# PERIPHERAL.net
KiCad netlist of a schematic drawn in Altium Designer
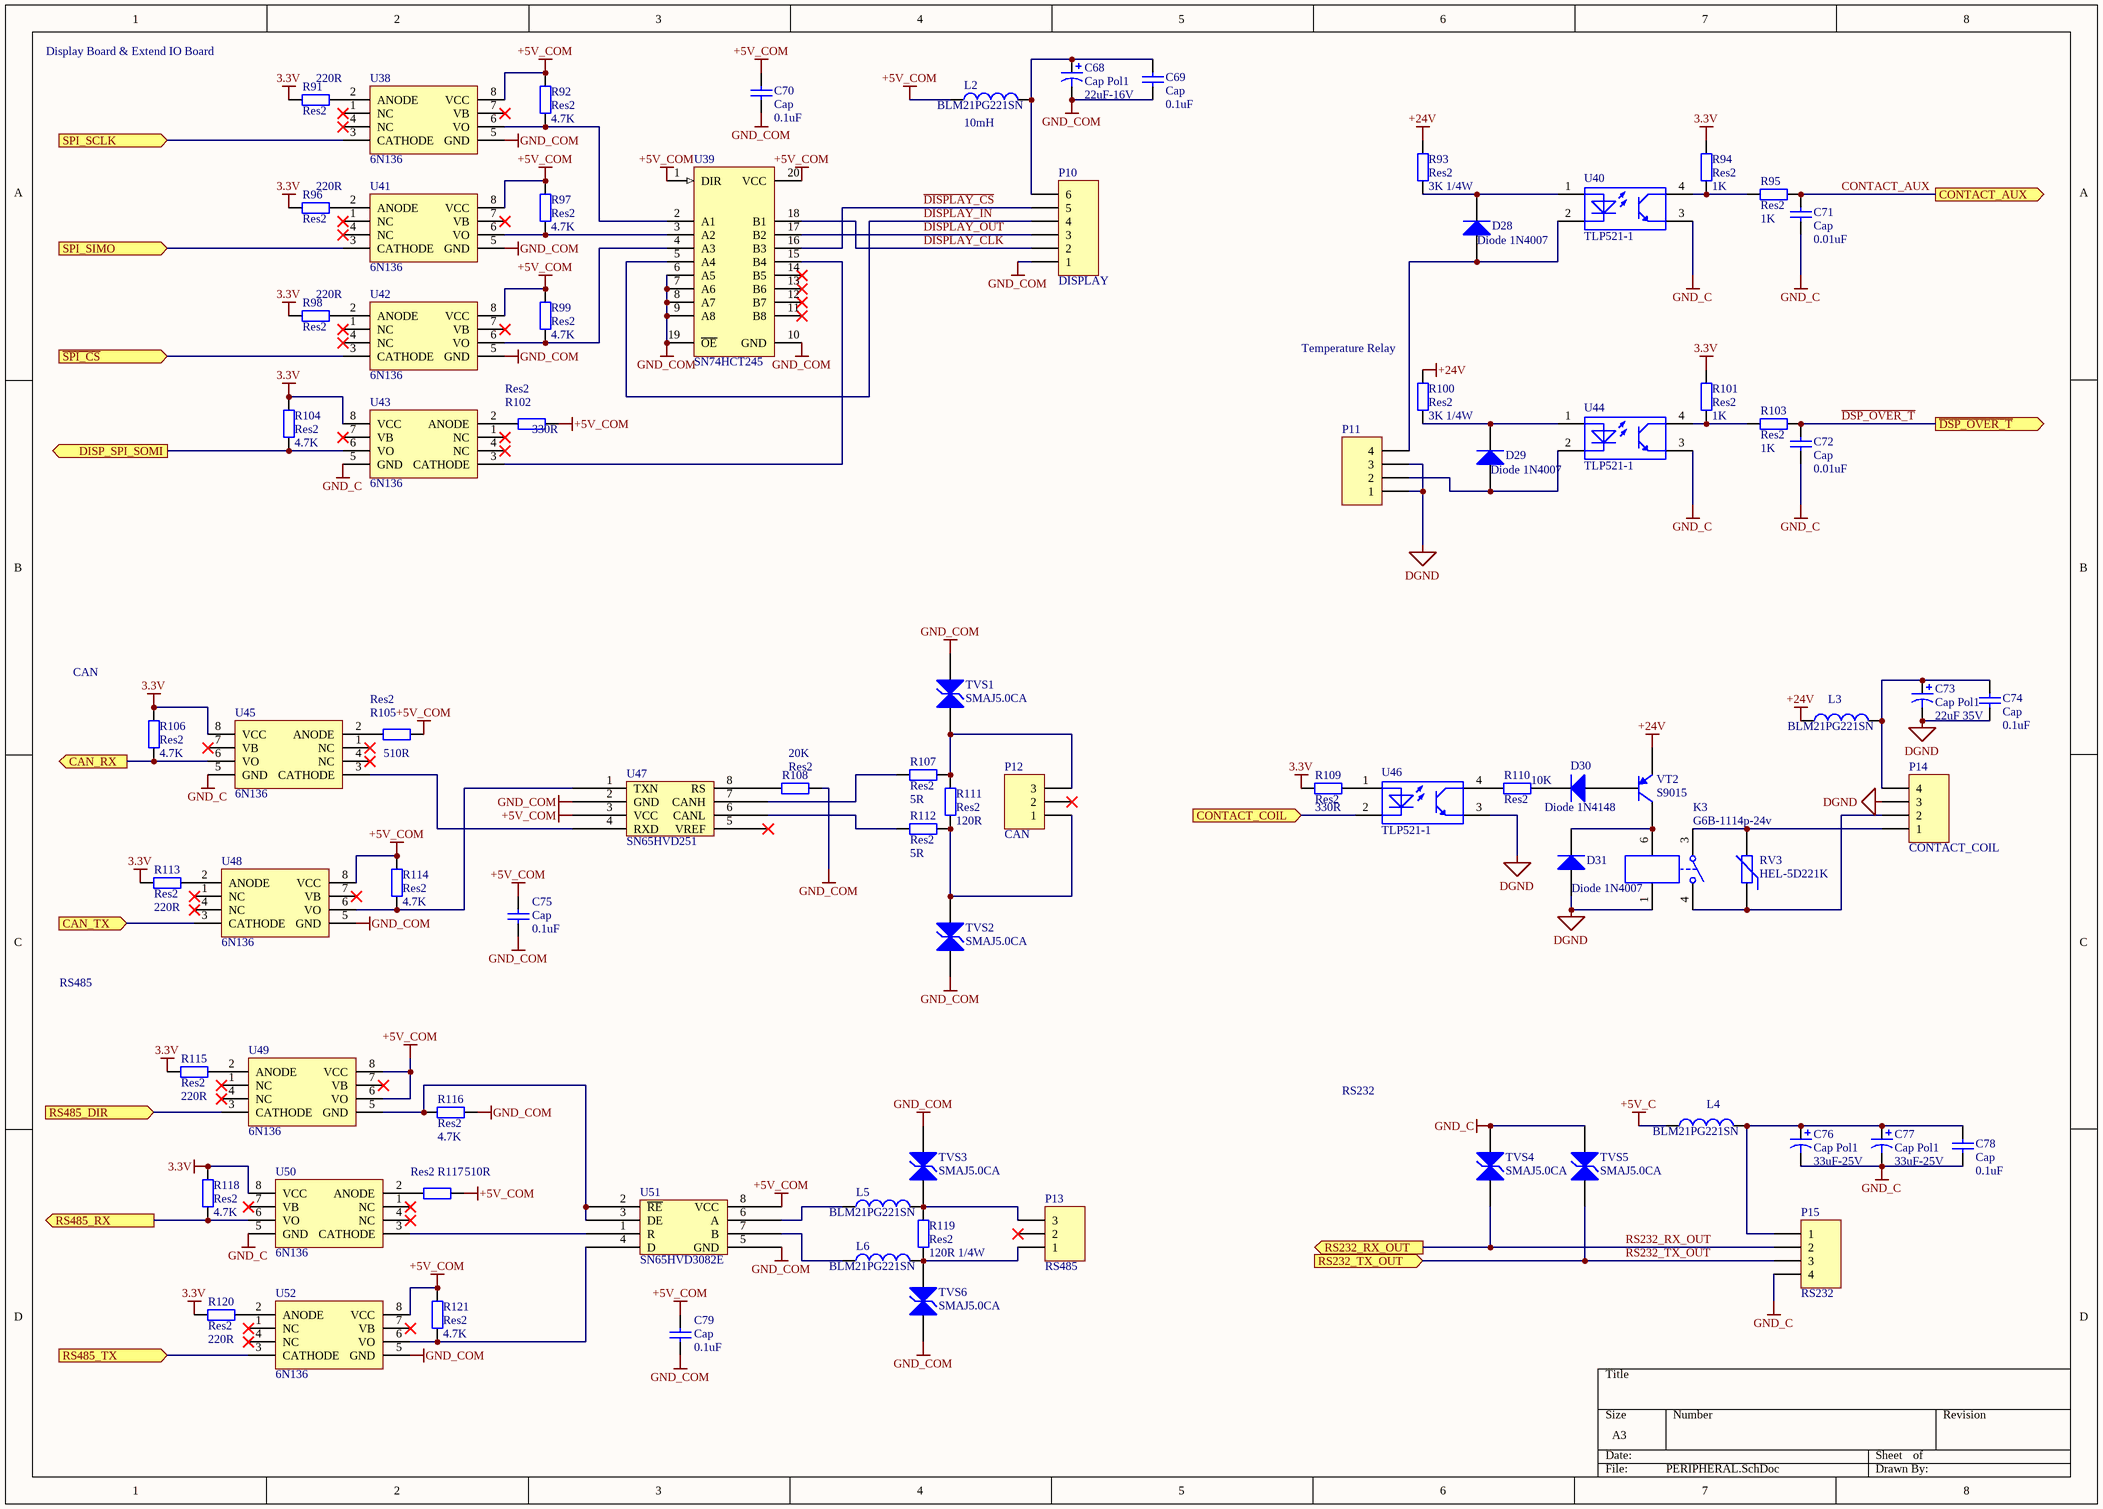
[diagram p0: PERIPHERAL.SchDoc]

(export (version "E")
  (design (tool "Eeschema 10.0.6"))
  (components
    (comp (ref "C68")
      (value "Cap Pol1")
      (footprint "7343")
      (description "Polarized Capacitor (Radial)")
      (fields (field (name "ALTIUM_VALUE") "22uF-16V") (field (name "PUBLISHER") "Altium Limited"))
      (libsource (lib "Miscellaneous Devices") (part "Cap Pol1"))
    )
    (comp (ref "C69")
      (value "Cap")
      (footprint "1206")
      (description "Capacitor")
      (fields (field (name "ALTIUM_VALUE") "0.1uF") (field (name "PUBLISHER") "Altium Limited"))
      (libsource (lib "Miscellaneous Devices") (part "Cap"))
    )
    (comp (ref "C70")
      (value "Cap")
      (footprint "1206")
      (description "Capacitor")
      (fields (field (name "ALTIUM_VALUE") "0.1uF") (field (name "PUBLISHER") "Altium Limited"))
      (libsource (lib "Miscellaneous Devices") (part "Cap"))
    )
    (comp (ref "C71")
      (value "Cap")
      (footprint "1206")
      (description "Capacitor")
      (fields (field (name "ALTIUM_VALUE") "0.01uF") (field (name "PUBLISHER") "Altium Limited"))
      (libsource (lib "Miscellaneous Devices") (part "Cap"))
    )
    (comp (ref "C72")
      (value "Cap")
      (footprint "1206")
      (description "Capacitor")
      (fields (field (name "ALTIUM_VALUE") "0.01uF") (field (name "PUBLISHER") "Altium Limited"))
      (libsource (lib "Miscellaneous Devices") (part "Cap"))
    )
    (comp (ref "C73")
      (value "Cap Pol1")
      (footprint "7343")
      (description "Polarized Capacitor (Radial)")
      (fields (field (name "ALTIUM_VALUE") "22uF 35V") (field (name "PUBLISHER") "Altium Limited"))
      (libsource (lib "Miscellaneous Devices") (part "Cap Pol1"))
    )
    (comp (ref "C74")
      (value "Cap")
      (footprint "1206")
      (description "Capacitor")
      (fields (field (name "ALTIUM_VALUE") "0.1uF") (field (name "PUBLISHER") "Altium Limited"))
      (libsource (lib "Miscellaneous Devices") (part "Cap"))
    )
    (comp (ref "C75")
      (value "Cap")
      (footprint "1206")
      (description "Capacitor")
      (fields (field (name "ALTIUM_VALUE") "0.1uF") (field (name "PUBLISHER") "Altium Limited"))
      (libsource (lib "Miscellaneous Devices") (part "Cap"))
    )
    (comp (ref "C76")
      (value "Cap Pol1")
      (footprint "7343")
      (description "Polarized Capacitor (Radial)")
      (fields (field (name "ALTIUM_VALUE") "33uF-25V") (field (name "PUBLISHER") "Altium Limited"))
      (libsource (lib "Miscellaneous Devices") (part "Cap Pol1"))
    )
    (comp (ref "C77")
      (value "Cap Pol1")
      (footprint "7343")
      (description "Polarized Capacitor (Radial)")
      (fields (field (name "ALTIUM_VALUE") "33uF-25V") (field (name "PUBLISHER") "Altium Limited"))
      (libsource (lib "Miscellaneous Devices") (part "Cap Pol1"))
    )
    (comp (ref "C78")
      (value "Cap")
      (footprint "1206")
      (description "Capacitor")
      (fields (field (name "ALTIUM_VALUE") "0.1uF") (field (name "PUBLISHER") "Altium Limited"))
      (libsource (lib "Miscellaneous Devices") (part "Cap"))
    )
    (comp (ref "C79")
      (value "Cap")
      (footprint "1206")
      (description "Capacitor")
      (fields (field (name "ALTIUM_VALUE") "0.1uF") (field (name "PUBLISHER") "Altium Limited"))
      (libsource (lib "Miscellaneous Devices") (part "Cap"))
    )
    (comp (ref "D28")
      (value "Diode 1N4007")
      (footprint "SMA")
      (description "1 Amp General Purpose Rectifier")
      (fields (field (name "PUBLISHER") "Altium Limited"))
      (libsource (lib "Miscellaneous Devices") (part "Diode 1N4007"))
    )
    (comp (ref "D29")
      (value "Diode 1N4007")
      (footprint "SMA")
      (description "1 Amp General Purpose Rectifier")
      (fields (field (name "PUBLISHER") "Altium Limited"))
      (libsource (lib "Miscellaneous Devices") (part "Diode 1N4007"))
    )
    (comp (ref "D30")
      (value "Diode 1N4148")
      (footprint "SOD-80/MLL34")
      (description "High Conductance Fast Diode")
      (fields (field (name "PUBLISHER") "Altium Limited"))
      (libsource (lib "Miscellaneous Devices") (part "Diode 1N4148"))
    )
    (comp (ref "D31")
      (value "Diode 1N4007")
      (footprint "SMA")
      (description "1 Amp General Purpose Rectifier")
      (fields (field (name "PUBLISHER") "Altium Limited"))
      (libsource (lib "Miscellaneous Devices") (part "Diode 1N4007"))
    )
    (comp (ref "K3")
      (value "G6B-1114p-24v")
      (footprint "SPST-NO")
      (description "Single-Pole Single-Throw Relay")
      (fields (field (name "PUBLISHER") "Altium Limited"))
      (libsource (lib "Miscellaneous Devices") (part "Relay-SPST"))
    )
    (comp (ref "L2")
      (value "BLM21PG221SN")
      (footprint "2012")
      (description "Inductor")
      (fields (field (name "ALTIUM_VALUE") "10mH") (field (name "PUBLISHER") "Altium Limited"))
      (libsource (lib "Miscellaneous Devices") (part "Inductor"))
    )
    (comp (ref "L3")
      (value "BLM21PG221SN")
      (footprint "2012")
      (libsource (lib "Schlib2") (part "BLM21PG221SN"))
    )
    (comp (ref "L4")
      (value "BLM21PG221SN")
      (footprint "2012")
      (description "Inductor")
      (fields (field (name "PUBLISHER") "Altium Limited"))
      (libsource (lib "Miscellaneous Devices") (part "Inductor"))
    )
    (comp (ref "L5")
      (value "BLM21PG221SN")
      (footprint "2012")
      (description "Inductor")
      (fields (field (name "PUBLISHER") "Altium Limited"))
      (libsource (lib "Miscellaneous Devices") (part "Inductor"))
    )
    (comp (ref "L6")
      (value "BLM21PG221SN")
      (footprint "2012")
      (description "Inductor")
      (fields (field (name "PUBLISHER") "Altium Limited"))
      (libsource (lib "Miscellaneous Devices") (part "Inductor"))
    )
    (comp (ref "P10")
      (value "DISPLAY")
      (footprint "phenox-6")
      (description "Header, 6-Pin")
      (fields (field (name "PUBLISHER") "Altium Limited"))
      (libsource (lib "Miscellaneous Connectors") (part "Header 6"))
    )
    (comp (ref "P11")
      (value "TR")
      (footprint "PHONEX-4")
      (description "Header, 4-Pin")
      (fields (field (name "PUBLISHER") "Altium Limited"))
      (libsource (lib "") (part "Header 4_2"))
    )
    (comp (ref "P12")
      (value "CAN")
      (footprint "PHENOX-3")
      (description "Header, 3-Pin")
      (fields (field (name "PUBLISHER") "Altium Limited"))
      (libsource (lib "") (part "Header 3_1"))
    )
    (comp (ref "P13")
      (value "RS485")
      (footprint "PHENOX-3")
      (description "Header, 3-Pin")
      (fields (field (name "PUBLISHER") "Altium Limited"))
      (libsource (lib "Miscellaneous Connectors") (part "Header 3"))
    )
    (comp (ref "P14")
      (value "CONTACT_COIL")
      (footprint "PHONEX-4")
      (description "Header, 4-Pin")
      (fields (field (name "PUBLISHER") "Altium Limited"))
      (libsource (lib "") (part "Header 4_1"))
    )
    (comp (ref "P15")
      (value "RS232")
      (footprint "PHONEX-4")
      (description "Header, 4-Pin")
      (fields (field (name "PUBLISHER") "Altium Limited"))
      (libsource (lib "Miscellaneous Connectors") (part "Header 4"))
    )
    (comp (ref "R91")
      (value "Res2")
      (footprint "1206")
      (description "Resistor")
      (fields (field (name "ALTIUM_VALUE") "220R") (field (name "PUBLISHER") "Altium Limited"))
      (libsource (lib "Miscellaneous Devices") (part "Res2"))
    )
    (comp (ref "R92")
      (value "Res2")
      (footprint "1206")
      (description "Resistor")
      (fields (field (name "ALTIUM_VALUE") "4.7K") (field (name "PUBLISHER") "Altium Limited"))
      (libsource (lib "") (part "Res2_1"))
    )
    (comp (ref "R93")
      (value "Res2")
      (footprint "1206")
      (description "Resistor")
      (fields (field (name "ALTIUM_VALUE") "3K 1/4W") (field (name "PUBLISHER") "Altium Limited"))
      (libsource (lib "") (part "Res2_1"))
    )
    (comp (ref "R94")
      (value "Res2")
      (footprint "1206")
      (description "Resistor")
      (fields (field (name "ALTIUM_VALUE") "1K") (field (name "PUBLISHER") "Altium Limited"))
      (libsource (lib "") (part "Res2_1"))
    )
    (comp (ref "R95")
      (value "Res2")
      (footprint "1206")
      (description "Resistor")
      (fields (field (name "ALTIUM_VALUE") "1K") (field (name "PUBLISHER") "Altium Limited"))
      (libsource (lib "") (part "Res2_2"))
    )
    (comp (ref "R96")
      (value "Res2")
      (footprint "1206")
      (description "Resistor")
      (fields (field (name "ALTIUM_VALUE") "220R") (field (name "PUBLISHER") "Altium Limited"))
      (libsource (lib "Miscellaneous Devices") (part "Res2"))
    )
    (comp (ref "R97")
      (value "Res2")
      (footprint "1206")
      (description "Resistor")
      (fields (field (name "ALTIUM_VALUE") "4.7K") (field (name "PUBLISHER") "Altium Limited"))
      (libsource (lib "") (part "Res2_1"))
    )
    (comp (ref "R98")
      (value "Res2")
      (footprint "1206")
      (description "Resistor")
      (fields (field (name "ALTIUM_VALUE") "220R") (field (name "PUBLISHER") "Altium Limited"))
      (libsource (lib "Miscellaneous Devices") (part "Res2"))
    )
    (comp (ref "R99")
      (value "Res2")
      (footprint "1206")
      (description "Resistor")
      (fields (field (name "ALTIUM_VALUE") "4.7K") (field (name "PUBLISHER") "Altium Limited"))
      (libsource (lib "") (part "Res2_1"))
    )
    (comp (ref "R100")
      (value "Res2")
      (footprint "1206")
      (description "Resistor")
      (fields (field (name "ALTIUM_VALUE") "3K 1/4W") (field (name "PUBLISHER") "Altium Limited"))
      (libsource (lib "") (part "Res2_1"))
    )
    (comp (ref "R101")
      (value "Res2")
      (footprint "1206")
      (description "Resistor")
      (fields (field (name "ALTIUM_VALUE") "1K") (field (name "PUBLISHER") "Altium Limited"))
      (libsource (lib "") (part "Res2_1"))
    )
    (comp (ref "R102")
      (value "Res2")
      (footprint "1206")
      (description "Resistor")
      (fields (field (name "ALTIUM_VALUE") "330R") (field (name "PUBLISHER") "Altium Limited"))
      (libsource (lib "") (part "Res2_2"))
    )
    (comp (ref "R103")
      (value "Res2")
      (footprint "1206")
      (description "Resistor")
      (fields (field (name "ALTIUM_VALUE") "1K") (field (name "PUBLISHER") "Altium Limited"))
      (libsource (lib "") (part "Res2_2"))
    )
    (comp (ref "R104")
      (value "Res2")
      (footprint "1206")
      (description "Resistor")
      (fields (field (name "ALTIUM_VALUE") "4.7K") (field (name "PUBLISHER") "Altium Limited"))
      (libsource (lib "") (part "Res2_1"))
    )
    (comp (ref "R105")
      (value "Res2")
      (footprint "1206")
      (description "Resistor")
      (fields (field (name "ALTIUM_VALUE") "510R") (field (name "PUBLISHER") "Altium Limited"))
      (libsource (lib "") (part "Res2_2"))
    )
    (comp (ref "R106")
      (value "Res2")
      (footprint "1206")
      (description "Resistor")
      (fields (field (name "ALTIUM_VALUE") "4.7K") (field (name "PUBLISHER") "Altium Limited"))
      (libsource (lib "") (part "Res2_1"))
    )
    (comp (ref "R107")
      (value "Res2")
      (footprint "1206")
      (description "Resistor")
      (fields (field (name "ALTIUM_VALUE") "5R") (field (name "PUBLISHER") "Altium Limited"))
      (libsource (lib "Miscellaneous Devices") (part "Res2"))
    )
    (comp (ref "R108")
      (value "Res2")
      (footprint "1206")
      (description "Resistor")
      (fields (field (name "ALTIUM_VALUE") "20K") (field (name "PUBLISHER") "Altium Limited"))
      (libsource (lib "Miscellaneous Devices") (part "Res2"))
    )
    (comp (ref "R109")
      (value "Res2")
      (footprint "1206")
      (description "Resistor")
      (fields (field (name "ALTIUM_VALUE") "330R") (field (name "PUBLISHER") "Altium Limited"))
      (libsource (lib "Miscellaneous Devices") (part "Res2"))
    )
    (comp (ref "R110")
      (value "Res2")
      (footprint "1206")
      (description "Resistor")
      (fields (field (name "ALTIUM_VALUE") "10K") (field (name "PUBLISHER") "Altium Limited"))
      (libsource (lib "Miscellaneous Devices") (part "Res2"))
    )
    (comp (ref "R111")
      (value "Res2")
      (footprint "1206")
      (description "Resistor")
      (fields (field (name "ALTIUM_VALUE") "120R") (field (name "PUBLISHER") "Altium Limited"))
      (libsource (lib "") (part "Res2_1"))
    )
    (comp (ref "R112")
      (value "Res2")
      (footprint "1206")
      (description "Resistor")
      (fields (field (name "ALTIUM_VALUE") "5R") (field (name "PUBLISHER") "Altium Limited"))
      (libsource (lib "Miscellaneous Devices") (part "Res2"))
    )
    (comp (ref "R113")
      (value "Res2")
      (footprint "1206")
      (description "Resistor")
      (fields (field (name "ALTIUM_VALUE") "220R") (field (name "PUBLISHER") "Altium Limited"))
      (libsource (lib "Miscellaneous Devices") (part "Res2"))
    )
    (comp (ref "R114")
      (value "Res2")
      (footprint "1206")
      (description "Resistor")
      (fields (field (name "ALTIUM_VALUE") "4.7K") (field (name "PUBLISHER") "Altium Limited"))
      (libsource (lib "") (part "Res2_1"))
    )
    (comp (ref "R115")
      (value "Res2")
      (footprint "1206")
      (description "Resistor")
      (fields (field (name "ALTIUM_VALUE") "220R") (field (name "PUBLISHER") "Altium Limited"))
      (libsource (lib "Miscellaneous Devices") (part "Res2"))
    )
    (comp (ref "R116")
      (value "Res2")
      (footprint "1206")
      (description "Resistor")
      (fields (field (name "ALTIUM_VALUE") "4.7K") (field (name "PUBLISHER") "Altium Limited"))
      (libsource (lib "Miscellaneous Devices") (part "Res2"))
    )
    (comp (ref "R117")
      (value "Res2")
      (footprint "1206")
      (description "Resistor")
      (fields (field (name "ALTIUM_VALUE") "510R") (field (name "PUBLISHER") "Altium Limited"))
      (libsource (lib "") (part "Res2_2"))
    )
    (comp (ref "R118")
      (value "Res2")
      (footprint "1206")
      (description "Resistor")
      (fields (field (name "ALTIUM_VALUE") "4.7K") (field (name "PUBLISHER") "Altium Limited"))
      (libsource (lib "") (part "Res2_1"))
    )
    (comp (ref "R119")
      (value "Res2")
      (footprint "1206")
      (description "Resistor")
      (fields (field (name "ALTIUM_VALUE") "120R 1/4W") (field (name "PUBLISHER") "Altium Limited"))
      (libsource (lib "") (part "Res2_1"))
    )
    (comp (ref "R120")
      (value "Res2")
      (footprint "1206")
      (description "Resistor")
      (fields (field (name "ALTIUM_VALUE") "220R") (field (name "PUBLISHER") "Altium Limited"))
      (libsource (lib "Miscellaneous Devices") (part "Res2"))
    )
    (comp (ref "R121")
      (value "Res2")
      (footprint "1206")
      (description "Resistor")
      (fields (field (name "ALTIUM_VALUE") "4.7K") (field (name "PUBLISHER") "Altium Limited"))
      (libsource (lib "") (part "Res2_1"))
    )
    (comp (ref "RV3")
      (value "HEL-5D221K")
      (footprint "RAD-0.2")
      (libsource (lib "Schlib2") (part "HEL-5D221K"))
    )
    (comp (ref "TVS1")
      (value "SMAJ5.0CA")
      (footprint "TVS-SMA")
      (libsource (lib "Schlib1") (part "SMAJ5.0CA"))
    )
    (comp (ref "TVS2")
      (value "SMAJ5.0CA")
      (footprint "TVS-SMA")
      (libsource (lib "Schlib1") (part "SMAJ5.0CA"))
    )
    (comp (ref "TVS3")
      (value "SMAJ5.0CA")
      (footprint "TVS-SMA")
      (libsource (lib "Schlib1") (part "SMAJ5.0CA"))
    )
    (comp (ref "TVS4")
      (value "SMAJ5.0CA")
      (footprint "TVS-SMA")
      (libsource (lib "Schlib1") (part "SMAJ5.0CA"))
    )
    (comp (ref "TVS5")
      (value "SMAJ5.0CA")
      (footprint "TVS-SMA")
      (libsource (lib "Schlib1") (part "SMAJ5.0CA"))
    )
    (comp (ref "TVS6")
      (value "SMAJ5.0CA")
      (footprint "TVS-SMA")
      (libsource (lib "Schlib1") (part "SMAJ5.0CA"))
    )
    (comp (ref "U38")
      (value "6N136")
      (footprint "DIP-8N")
      (description "光耦")
      (libsource (lib "Integrated_Library1") (part "6N136"))
    )
    (comp (ref "U39")
      (value "SN74HCT245")
      (footprint "SO20_M")
      (libsource (lib "Schlib2") (part "SN74HCT245"))
    )
    (comp (ref "U40") (value "TLP521-1") (footprint "DIP4") (libsource (lib "单片机及相关") (part "TLP521-1")))
    (comp (ref "U41")
      (value "6N136")
      (footprint "DIP-8N")
      (description "光耦")
      (libsource (lib "Integrated_Library1") (part "6N136"))
    )
    (comp (ref "U42")
      (value "6N136")
      (footprint "DIP-8N")
      (description "光耦")
      (libsource (lib "Integrated_Library1") (part "6N136"))
    )
    (comp (ref "U43")
      (value "6N136")
      (footprint "DIP-8N")
      (description "光耦")
      (libsource (lib "") (part "6N136_1"))
    )
    (comp (ref "U44") (value "TLP521-1") (footprint "DIP4") (libsource (lib "单片机及相关") (part "TLP521-1")))
    (comp (ref "U45")
      (value "6N136")
      (footprint "DIP-8N")
      (description "光耦")
      (libsource (lib "") (part "6N136_1"))
    )
    (comp (ref "U46") (value "TLP521-1") (footprint "DIP4") (libsource (lib "单片机及相关") (part "TLP521-1")))
    (comp (ref "U47") (value "SN65HVD251") (footprint "SO-8") (libsource (lib "Schlib1") (part "SN65HVD251")))
    (comp (ref "U48")
      (value "6N136")
      (footprint "DIP-8N")
      (description "光耦")
      (libsource (lib "Integrated_Library1") (part "6N136"))
    )
    (comp (ref "U49")
      (value "6N136")
      (footprint "DIP-8N")
      (description "光耦")
      (libsource (lib "Integrated_Library1") (part "6N136"))
    )
    (comp (ref "U50")
      (value "6N136")
      (footprint "DIP-8N")
      (description "光耦")
      (libsource (lib "") (part "6N136_1"))
    )
    (comp (ref "U51")
      (value "SN65HVD3082E")
      (footprint "SO-8")
      (libsource (lib "Schlib1") (part "SN65HVD3082E"))
    )
    (comp (ref "U52")
      (value "6N136")
      (footprint "DIP-8N")
      (description "光耦")
      (libsource (lib "Integrated_Library1") (part "6N136"))
    )
    (comp (ref "VT2") (value "S9015") (footprint "SOT23") (libsource (lib "Schlib2") (part "S9015")))
  )
  (nets
    (net (code "1") (name "+5V_C") (class "Default")
      (node (ref "L4") (pin "1") (pinfunction "1_1") (pintype "passive"))
    )
    (net (code "2") (name "+5V_COM") (class "Default")
      (node (ref "C70") (pin "2") (pinfunction "2_2") (pintype "passive"))
      (node (ref "C75") (pin "2") (pinfunction "2_2") (pintype "passive"))
      (node (ref "C79") (pin "2") (pinfunction "2_2") (pintype "passive"))
      (node (ref "L2") (pin "1") (pinfunction "1_1") (pintype "passive"))
      (node (ref "R102") (pin "1") (pinfunction "1_1") (pintype "passive"))
      (node (ref "R105") (pin "1") (pinfunction "1_1") (pintype "passive"))
      (node (ref "R114") (pin "2") (pinfunction "2_2") (pintype "passive"))
      (node (ref "R117") (pin "1") (pinfunction "1_1") (pintype "passive"))
      (node (ref "R121") (pin "2") (pinfunction "2_2") (pintype "passive"))
      (node (ref "R92") (pin "2") (pinfunction "2_2") (pintype "passive"))
      (node (ref "R97") (pin "2") (pinfunction "2_2") (pintype "passive"))
      (node (ref "R99") (pin "2") (pinfunction "2_2") (pintype "passive"))
      (node (ref "U38") (pin "8") (pinfunction "VCC_8") (pintype "power_in"))
      (node (ref "U39") (pin "1") (pinfunction "DIR_1") (pintype "input"))
      (node (ref "U39") (pin "20") (pinfunction "VCC_20") (pintype "power_in"))
      (node (ref "U41") (pin "8") (pinfunction "VCC_8") (pintype "power_in"))
      (node (ref "U42") (pin "8") (pinfunction "VCC_8") (pintype "power_in"))
      (node (ref "U47") (pin "3") (pinfunction "VCC_3") (pintype "passive"))
      (node (ref "U48") (pin "8") (pinfunction "VCC_8") (pintype "power_in"))
      (node (ref "U49") (pin "6") (pinfunction "VO_6") (pintype "passive"))
      (node (ref "U49") (pin "8") (pinfunction "VCC_8") (pintype "power_in"))
      (node (ref "U51") (pin "8") (pinfunction "VCC_8") (pintype "passive"))
      (node (ref "U52") (pin "8") (pinfunction "VCC_8") (pintype "power_in"))
    )
    (net (code "3") (name "+24V") (class "Default")
      (node (ref "L3") (pin "1") (pinfunction "1_1") (pintype "passive"))
      (node (ref "R100") (pin "2") (pinfunction "2_2") (pintype "passive"))
      (node (ref "R93") (pin "2") (pinfunction "2_2") (pintype "passive"))
      (node (ref "VT2") (pin "3") (pinfunction "E_3") (pintype "passive"))
    )
    (net (code "4") (name "/CAN_RX") (class "Default")
      (node (ref "R106") (pin "1") (pinfunction "1_1") (pintype "passive"))
      (node (ref "U45") (pin "6") (pinfunction "VO_6") (pintype "passive"))
    )
    (net (code "5") (name "/CAN_TX") (class "Default")
      (node (ref "U48") (pin "3") (pinfunction "CATHODE_3") (pintype "passive"))
    )
    (net (code "6") (name "/CONTACT_AUX") (class "Default")
      (node (ref "C71") (pin "2") (pinfunction "2_2") (pintype "passive"))
      (node (ref "R95") (pin "1") (pinfunction "1_1") (pintype "passive"))
    )
    (net (code "7") (name "/CONTACT_COIL") (class "Default")
      (node (ref "U46") (pin "2") (pinfunction "2_2") (pintype "passive"))
    )
    (net (code "8") (name "/DISPLAY_CLK") (class "Default")
      (node (ref "P10") (pin "2") (pinfunction "2_2") (pintype "passive"))
      (node (ref "U39") (pin "18") (pinfunction "B1_18") (pintype "passive"))
    )
    (net (code "9") (name "/DISPLAY_IN") (class "Default")
      (node (ref "P10") (pin "4") (pinfunction "4_4") (pintype "passive"))
      (node (ref "U39") (pin "5") (pinfunction "A4_5") (pintype "passive"))
    )
    (net (code "10") (name "/DISPLAY_OUT") (class "Default")
      (node (ref "P10") (pin "3") (pinfunction "3_3") (pintype "passive"))
      (node (ref "U39") (pin "17") (pinfunction "B2_17") (pintype "passive"))
    )
    (net (code "11") (name "/DISP_SPI_SOMI") (class "Default")
      (node (ref "R104") (pin "1") (pinfunction "1_1") (pintype "passive"))
      (node (ref "U43") (pin "6") (pinfunction "VO_6") (pintype "passive"))
    )
    (net (code "12") (name "/RS232_RX_OUT") (class "Default")
      (node (ref "P15") (pin "2") (pinfunction "2_2") (pintype "passive"))
      (node (ref "TVS4") (pin "1") (pinfunction "A_1") (pintype "passive"))
    )
    (net (code "13") (name "/RS232_TX_OUT") (class "Default")
      (node (ref "P15") (pin "3") (pinfunction "3_3") (pintype "passive"))
      (node (ref "TVS5") (pin "1") (pinfunction "A_1") (pintype "passive"))
    )
    (net (code "14") (name "/RS485_DIR") (class "Default")
      (node (ref "U49") (pin "3") (pinfunction "CATHODE_3") (pintype "passive"))
    )
    (net (code "15") (name "/RS485_RX") (class "Default")
      (node (ref "R118") (pin "1") (pinfunction "1_1") (pintype "passive"))
      (node (ref "U50") (pin "6") (pinfunction "VO_6") (pintype "passive"))
    )
    (net (code "16") (name "/RS485_TX") (class "Default")
      (node (ref "U52") (pin "3") (pinfunction "CATHODE_3") (pintype "passive"))
    )
    (net (code "17") (name "/SPI_SCLK") (class "Default")
      (node (ref "U38") (pin "3") (pinfunction "CATHODE_3") (pintype "passive"))
    )
    (net (code "18") (name "/SPI_SIMO") (class "Default")
      (node (ref "U41") (pin "3") (pinfunction "CATHODE_3") (pintype "passive"))
    )
    (net (code "19") (name "/~{DISPLAY_CS}") (class "Default")
      (node (ref "P10") (pin "5") (pinfunction "5_5") (pintype "passive"))
      (node (ref "U39") (pin "16") (pinfunction "B3_16") (pintype "passive"))
    )
    (net (code "20") (name "/~{DSP_OVER_T}") (class "Default")
      (node (ref "C72") (pin "2") (pinfunction "2_2") (pintype "passive"))
      (node (ref "R103") (pin "1") (pinfunction "1_1") (pintype "passive"))
    )
    (net (code "21") (name "/~{SPI_CS}") (class "Default")
      (node (ref "U42") (pin "3") (pinfunction "CATHODE_3") (pintype "passive"))
    )
    (net (code "22") (name "3.3V") (class "Default")
      (node (ref "R101") (pin "2") (pinfunction "2_2") (pintype "passive"))
      (node (ref "R104") (pin "2") (pinfunction "2_2") (pintype "passive"))
      (node (ref "R106") (pin "2") (pinfunction "2_2") (pintype "passive"))
      (node (ref "R109") (pin "1") (pinfunction "1_1") (pintype "passive"))
      (node (ref "R113") (pin "1") (pinfunction "1_1") (pintype "passive"))
      (node (ref "R115") (pin "1") (pinfunction "1_1") (pintype "passive"))
      (node (ref "R118") (pin "2") (pinfunction "2_2") (pintype "passive"))
      (node (ref "R120") (pin "1") (pinfunction "1_1") (pintype "passive"))
      (node (ref "R91") (pin "1") (pinfunction "1_1") (pintype "passive"))
      (node (ref "R94") (pin "2") (pinfunction "2_2") (pintype "passive"))
      (node (ref "R96") (pin "1") (pinfunction "1_1") (pintype "passive"))
      (node (ref "R98") (pin "1") (pinfunction "1_1") (pintype "passive"))
      (node (ref "U43") (pin "8") (pinfunction "VCC_8") (pintype "power_in"))
      (node (ref "U45") (pin "8") (pinfunction "VCC_8") (pintype "power_in"))
      (node (ref "U50") (pin "8") (pinfunction "VCC_8") (pintype "power_in"))
    )
    (net (code "23") (name "DGND") (class "Default")
      (node (ref "C73") (pin "2") (pinfunction "2_2") (pintype "passive"))
      (node (ref "C74") (pin "1") (pinfunction "1_1") (pintype "passive"))
      (node (ref "D31") (pin "1") (pinfunction "A_1") (pintype "passive"))
      (node (ref "K3") (pin "1") (pinfunction "1_1") (pintype "passive"))
      (node (ref "P11") (pin "1") (pinfunction "1_1") (pintype "passive"))
      (node (ref "P11") (pin "3") (pinfunction "3_3") (pintype "passive"))
      (node (ref "P14") (pin "3") (pinfunction "3_3") (pintype "passive"))
      (node (ref "U46") (pin "3") (pinfunction "3_3") (pintype "passive"))
    )
    (net (code "24") (name "GND_C") (class "Default")
      (node (ref "C71") (pin "1") (pinfunction "1_1") (pintype "passive"))
      (node (ref "C72") (pin "1") (pinfunction "1_1") (pintype "passive"))
      (node (ref "C76") (pin "2") (pinfunction "2_2") (pintype "passive"))
      (node (ref "C77") (pin "2") (pinfunction "2_2") (pintype "passive"))
      (node (ref "C78") (pin "1") (pinfunction "1_1") (pintype "passive"))
      (node (ref "P15") (pin "4") (pinfunction "4_4") (pintype "passive"))
      (node (ref "TVS4") (pin "2") (pinfunction "K_2") (pintype "passive"))
      (node (ref "TVS5") (pin "2") (pinfunction "K_2") (pintype "passive"))
      (node (ref "U40") (pin "3") (pinfunction "3_3") (pintype "passive"))
      (node (ref "U43") (pin "5") (pinfunction "GND_5") (pintype "passive"))
      (node (ref "U44") (pin "3") (pinfunction "3_3") (pintype "passive"))
      (node (ref "U45") (pin "5") (pinfunction "GND_5") (pintype "passive"))
      (node (ref "U50") (pin "5") (pinfunction "GND_5") (pintype "passive"))
    )
    (net (code "25") (name "GND_COM") (class "Default")
      (node (ref "C68") (pin "2") (pinfunction "2_2") (pintype "passive"))
      (node (ref "C69") (pin "1") (pinfunction "1_1") (pintype "passive"))
      (node (ref "C70") (pin "1") (pinfunction "1_1") (pintype "passive"))
      (node (ref "C75") (pin "1") (pinfunction "1_1") (pintype "passive"))
      (node (ref "C79") (pin "1") (pinfunction "1_1") (pintype "passive"))
      (node (ref "P10") (pin "1") (pinfunction "1_1") (pintype "passive"))
      (node (ref "R108") (pin "2") (pinfunction "2_2") (pintype "passive"))
      (node (ref "R116") (pin "2") (pinfunction "2_2") (pintype "passive"))
      (node (ref "TVS1") (pin "2") (pinfunction "K_2") (pintype "passive"))
      (node (ref "TVS2") (pin "1") (pinfunction "A_1") (pintype "passive"))
      (node (ref "TVS3") (pin "1") (pinfunction "A_1") (pintype "passive"))
      (node (ref "TVS6") (pin "2") (pinfunction "K_2") (pintype "passive"))
      (node (ref "U38") (pin "5") (pinfunction "GND_5") (pintype "passive"))
      (node (ref "U39") (pin "10") (pinfunction "GND_10") (pintype "passive"))
      (node (ref "U39") (pin "19") (pinfunction "~{OE}_19") (pintype "passive"))
      (node (ref "U39") (pin "6") (pinfunction "A5_6") (pintype "passive"))
      (node (ref "U39") (pin "7") (pinfunction "A6_7") (pintype "passive"))
      (node (ref "U39") (pin "8") (pinfunction "A7_8") (pintype "passive"))
      (node (ref "U39") (pin "9") (pinfunction "A8_9") (pintype "passive"))
      (node (ref "U41") (pin "5") (pinfunction "GND_5") (pintype "passive"))
      (node (ref "U42") (pin "5") (pinfunction "GND_5") (pintype "passive"))
      (node (ref "U47") (pin "2") (pinfunction "GND_2") (pintype "passive"))
      (node (ref "U48") (pin "5") (pinfunction "GND_5") (pintype "passive"))
      (node (ref "U51") (pin "5") (pinfunction "GND_5") (pintype "passive"))
      (node (ref "U52") (pin "5") (pinfunction "GND_5") (pintype "passive"))
    )
    (net (code "26") (name "Net-(C68-Pad1)") (class "Default")
      (node (ref "C68") (pin "1") (pinfunction "1_1") (pintype "passive"))
      (node (ref "C69") (pin "2") (pinfunction "2_2") (pintype "passive"))
      (node (ref "L2") (pin "2") (pinfunction "2_2") (pintype "passive"))
      (node (ref "P10") (pin "6") (pinfunction "6_6") (pintype "passive"))
    )
    (net (code "27") (name "Net-(C73-Pad1)") (class "Default")
      (node (ref "C73") (pin "1") (pinfunction "1_1") (pintype "passive"))
      (node (ref "C74") (pin "2") (pinfunction "2_2") (pintype "passive"))
      (node (ref "L3") (pin "2") (pinfunction "2_2") (pintype "passive"))
      (node (ref "P14") (pin "4") (pinfunction "4_4") (pintype "passive"))
    )
    (net (code "28") (name "Net-(C76-Pad1)") (class "Default")
      (node (ref "C76") (pin "1") (pinfunction "1_1") (pintype "passive"))
      (node (ref "C77") (pin "1") (pinfunction "1_1") (pintype "passive"))
      (node (ref "C78") (pin "2") (pinfunction "2_2") (pintype "passive"))
      (node (ref "L4") (pin "2") (pinfunction "2_2") (pintype "passive"))
      (node (ref "P15") (pin "1") (pinfunction "1_1") (pintype "passive"))
    )
    (net (code "29") (name "Net-(D28-A)") (class "Default")
      (node (ref "D28") (pin "1") (pinfunction "A_1") (pintype "passive"))
      (node (ref "P11") (pin "4") (pinfunction "4_4") (pintype "passive"))
      (node (ref "U40") (pin "2") (pinfunction "2_2") (pintype "passive"))
    )
    (net (code "30") (name "Net-(D28-K)") (class "Default")
      (node (ref "D28") (pin "2") (pinfunction "K_2") (pintype "passive"))
      (node (ref "R93") (pin "1") (pinfunction "1_1") (pintype "passive"))
      (node (ref "U40") (pin "1") (pinfunction "1_1") (pintype "passive"))
    )
    (net (code "31") (name "Net-(D29-A)") (class "Default")
      (node (ref "D29") (pin "1") (pinfunction "A_1") (pintype "passive"))
      (node (ref "P11") (pin "2") (pinfunction "2_2") (pintype "passive"))
      (node (ref "U44") (pin "2") (pinfunction "2_2") (pintype "passive"))
    )
    (net (code "32") (name "Net-(D29-K)") (class "Default")
      (node (ref "D29") (pin "2") (pinfunction "K_2") (pintype "passive"))
      (node (ref "R100") (pin "1") (pinfunction "1_1") (pintype "passive"))
      (node (ref "U44") (pin "1") (pinfunction "1_1") (pintype "passive"))
    )
    (net (code "33") (name "Net-(D30-A)") (class "Default")
      (node (ref "D30") (pin "1") (pinfunction "A_1") (pintype "passive"))
      (node (ref "VT2") (pin "2") (pinfunction "B_2") (pintype "passive"))
    )
    (net (code "34") (name "Net-(D30-K)") (class "Default")
      (node (ref "D30") (pin "2") (pinfunction "K_2") (pintype "passive"))
      (node (ref "R110") (pin "2") (pinfunction "2_2") (pintype "passive"))
    )
    (net (code "35") (name "Net-(D31-K)") (class "Default")
      (node (ref "D31") (pin "2") (pinfunction "K_2") (pintype "passive"))
      (node (ref "K3") (pin "6") (pinfunction "6_6") (pintype "passive"))
      (node (ref "VT2") (pin "1") (pinfunction "C_1") (pintype "passive"))
    )
    (net (code "36") (name "Net-(K3-Pad3)") (class "Default")
      (node (ref "K3") (pin "3") (pinfunction "3_3") (pintype "passive"))
      (node (ref "P14") (pin "1") (pinfunction "1_1") (pintype "passive"))
      (node (ref "RV3") (pin "2") (pinfunction "2_2") (pintype "passive"))
    )
    (net (code "37") (name "Net-(K3-Pad4)") (class "Default")
      (node (ref "K3") (pin "4") (pinfunction "4_4") (pintype "passive"))
      (node (ref "P14") (pin "2") (pinfunction "2_2") (pintype "passive"))
      (node (ref "RV3") (pin "1") (pinfunction "1_1") (pintype "passive"))
    )
    (net (code "38") (name "Net-(R94-Pad1)") (class "Default")
      (node (ref "R94") (pin "1") (pinfunction "1_1") (pintype "passive"))
      (node (ref "R95") (pin "2") (pinfunction "2_2") (pintype "passive"))
      (node (ref "U40") (pin "4") (pinfunction "4_4") (pintype "passive"))
    )
    (net (code "39") (name "Net-(R101-Pad1)") (class "Default")
      (node (ref "R101") (pin "1") (pinfunction "1_1") (pintype "passive"))
      (node (ref "R103") (pin "2") (pinfunction "2_2") (pintype "passive"))
      (node (ref "U44") (pin "4") (pinfunction "4_4") (pintype "passive"))
    )
    (net (code "40") (name "Net-(R109-Pad2)") (class "Default")
      (node (ref "R109") (pin "2") (pinfunction "2_2") (pintype "passive"))
      (node (ref "U46") (pin "1") (pinfunction "1_1") (pintype "passive"))
    )
    (net (code "41") (name "Net-(R110-Pad1)") (class "Default")
      (node (ref "R110") (pin "1") (pinfunction "1_1") (pintype "passive"))
      (node (ref "U46") (pin "4") (pinfunction "4_4") (pintype "passive"))
    )
    (net (code "42") (name "Net-(TVS1-A)") (class "Default")
      (node (ref "P12") (pin "3") (pinfunction "3_3") (pintype "passive"))
      (node (ref "R107") (pin "2") (pinfunction "2_2") (pintype "passive"))
      (node (ref "R111") (pin "2") (pinfunction "2_2") (pintype "passive"))
      (node (ref "TVS1") (pin "1") (pinfunction "A_1") (pintype "passive"))
    )
    (net (code "43") (name "Net-(TVS2-K)") (class "Default")
      (node (ref "P12") (pin "1") (pinfunction "1_1") (pintype "passive"))
      (node (ref "R111") (pin "1") (pinfunction "1_1") (pintype "passive"))
      (node (ref "R112") (pin "2") (pinfunction "2_2") (pintype "passive"))
      (node (ref "TVS2") (pin "2") (pinfunction "K_2") (pintype "passive"))
    )
    (net (code "44") (name "Net-(TVS3-K)") (class "Default")
      (node (ref "L5") (pin "2") (pinfunction "2_2") (pintype "passive"))
      (node (ref "P13") (pin "3") (pinfunction "3_3") (pintype "passive"))
      (node (ref "R119") (pin "2") (pinfunction "2_2") (pintype "passive"))
      (node (ref "TVS3") (pin "2") (pinfunction "K_2") (pintype "passive"))
    )
    (net (code "45") (name "Net-(TVS6-A)") (class "Default")
      (node (ref "L6") (pin "2") (pinfunction "2_2") (pintype "passive"))
      (node (ref "P13") (pin "1") (pinfunction "1_1") (pintype "passive"))
      (node (ref "R119") (pin "1") (pinfunction "1_1") (pintype "passive"))
      (node (ref "TVS6") (pin "1") (pinfunction "A_1") (pintype "passive"))
    )
    (net (code "46") (name "Net-(U38-ANODE)") (class "Default")
      (node (ref "R91") (pin "2") (pinfunction "2_2") (pintype "passive"))
      (node (ref "U38") (pin "2") (pinfunction "ANODE_2") (pintype "passive"))
    )
    (net (code "47") (name "Net-(U38-VO)") (class "Default")
      (node (ref "R92") (pin "1") (pinfunction "1_1") (pintype "passive"))
      (node (ref "U38") (pin "6") (pinfunction "VO_6") (pintype "passive"))
      (node (ref "U39") (pin "2") (pinfunction "A1_2") (pintype "passive"))
    )
    (net (code "48") (name "Net-(U39-A2)") (class "Default")
      (node (ref "R97") (pin "1") (pinfunction "1_1") (pintype "passive"))
      (node (ref "U39") (pin "3") (pinfunction "A2_3") (pintype "passive"))
      (node (ref "U41") (pin "6") (pinfunction "VO_6") (pintype "passive"))
    )
    (net (code "49") (name "Net-(U39-A3)") (class "Default")
      (node (ref "R99") (pin "1") (pinfunction "1_1") (pintype "passive"))
      (node (ref "U39") (pin "4") (pinfunction "A3_4") (pintype "passive"))
      (node (ref "U42") (pin "6") (pinfunction "VO_6") (pintype "passive"))
    )
    (net (code "50") (name "Net-(U39-B4)") (class "Default")
      (node (ref "U39") (pin "15") (pinfunction "B4_15") (pintype "passive"))
      (node (ref "U43") (pin "3") (pinfunction "CATHODE_3") (pintype "passive"))
    )
    (net (code "51") (name "Net-(U41-ANODE)") (class "Default")
      (node (ref "R96") (pin "2") (pinfunction "2_2") (pintype "passive"))
      (node (ref "U41") (pin "2") (pinfunction "ANODE_2") (pintype "passive"))
    )
    (net (code "52") (name "Net-(U42-ANODE)") (class "Default")
      (node (ref "R98") (pin "2") (pinfunction "2_2") (pintype "passive"))
      (node (ref "U42") (pin "2") (pinfunction "ANODE_2") (pintype "passive"))
    )
    (net (code "53") (name "Net-(U43-ANODE)") (class "Default")
      (node (ref "R102") (pin "2") (pinfunction "2_2") (pintype "passive"))
      (node (ref "U43") (pin "2") (pinfunction "ANODE_2") (pintype "passive"))
    )
    (net (code "54") (name "Net-(U45-ANODE)") (class "Default")
      (node (ref "R105") (pin "2") (pinfunction "2_2") (pintype "passive"))
      (node (ref "U45") (pin "2") (pinfunction "ANODE_2") (pintype "passive"))
    )
    (net (code "55") (name "Net-(U45-CATHODE)") (class "Default")
      (node (ref "U45") (pin "3") (pinfunction "CATHODE_3") (pintype "passive"))
      (node (ref "U47") (pin "4") (pinfunction "RXD_4") (pintype "passive"))
    )
    (net (code "56") (name "Net-(U47-CANH)") (class "Default")
      (node (ref "R107") (pin "1") (pinfunction "1_1") (pintype "passive"))
      (node (ref "U47") (pin "7") (pinfunction "CANH_7") (pintype "passive"))
    )
    (net (code "57") (name "Net-(U47-CANL)") (class "Default")
      (node (ref "R112") (pin "1") (pinfunction "1_1") (pintype "passive"))
      (node (ref "U47") (pin "6") (pinfunction "CANL_6") (pintype "passive"))
    )
    (net (code "58") (name "Net-(U47-RS)") (class "Default")
      (node (ref "R108") (pin "1") (pinfunction "1_1") (pintype "passive"))
      (node (ref "U47") (pin "8") (pinfunction "RS_8") (pintype "passive"))
    )
    (net (code "59") (name "Net-(U47-TXN)") (class "Default")
      (node (ref "R114") (pin "1") (pinfunction "1_1") (pintype "passive"))
      (node (ref "U47") (pin "1") (pinfunction "TXN_1") (pintype "passive"))
      (node (ref "U48") (pin "6") (pinfunction "VO_6") (pintype "passive"))
    )
    (net (code "60") (name "Net-(U48-ANODE)") (class "Default")
      (node (ref "R113") (pin "2") (pinfunction "2_2") (pintype "passive"))
      (node (ref "U48") (pin "2") (pinfunction "ANODE_2") (pintype "passive"))
    )
    (net (code "61") (name "Net-(U49-ANODE)") (class "Default")
      (node (ref "R115") (pin "2") (pinfunction "2_2") (pintype "passive"))
      (node (ref "U49") (pin "2") (pinfunction "ANODE_2") (pintype "passive"))
    )
    (net (code "62") (name "Net-(U49-GND)") (class "Default")
      (node (ref "R116") (pin "1") (pinfunction "1_1") (pintype "passive"))
      (node (ref "U49") (pin "5") (pinfunction "GND_5") (pintype "passive"))
      (node (ref "U51") (pin "2") (pinfunction "~{RE}_2") (pintype "passive"))
      (node (ref "U51") (pin "3") (pinfunction "DE_3") (pintype "passive"))
    )
    (net (code "63") (name "Net-(U50-ANODE)") (class "Default")
      (node (ref "R117") (pin "2") (pinfunction "2_2") (pintype "passive"))
      (node (ref "U50") (pin "2") (pinfunction "ANODE_2") (pintype "passive"))
    )
    (net (code "64") (name "Net-(U50-CATHODE)") (class "Default")
      (node (ref "U50") (pin "3") (pinfunction "CATHODE_3") (pintype "passive"))
      (node (ref "U51") (pin "1") (pinfunction "R_1") (pintype "passive"))
    )
    (net (code "65") (name "Net-(U51-A)") (class "Default")
      (node (ref "L5") (pin "1") (pinfunction "1_1") (pintype "passive"))
      (node (ref "U51") (pin "6") (pinfunction "A_6") (pintype "passive"))
    )
    (net (code "66") (name "Net-(U51-B)") (class "Default")
      (node (ref "L6") (pin "1") (pinfunction "1_1") (pintype "passive"))
      (node (ref "U51") (pin "7") (pinfunction "B_7") (pintype "passive"))
    )
    (net (code "67") (name "Net-(U51-D)") (class "Default")
      (node (ref "R121") (pin "1") (pinfunction "1_1") (pintype "passive"))
      (node (ref "U51") (pin "4") (pinfunction "D_4") (pintype "passive"))
      (node (ref "U52") (pin "6") (pinfunction "VO_6") (pintype "passive"))
    )
    (net (code "68") (name "Net-(U52-ANODE)") (class "Default")
      (node (ref "R120") (pin "2") (pinfunction "2_2") (pintype "passive"))
      (node (ref "U52") (pin "2") (pinfunction "ANODE_2") (pintype "passive"))
    )
    (net (code "69") (name "unconnected-(P12-Pad2)") (class "Default")
      (node (ref "P12") (pin "2") (pinfunction "2_2") (pintype "passive+no_connect"))
    )
    (net (code "70") (name "unconnected-(P13-Pad2)") (class "Default")
      (node (ref "P13") (pin "2") (pinfunction "2_2") (pintype "passive+no_connect"))
    )
    (net (code "71") (name "unconnected-(U38-NC-Pad1)") (class "Default")
      (node (ref "U38") (pin "1") (pinfunction "NC_1") (pintype "passive+no_connect"))
    )
    (net (code "72") (name "unconnected-(U38-NC-Pad4)") (class "Default")
      (node (ref "U38") (pin "4") (pinfunction "NC_4") (pintype "power_in+no_connect"))
    )
    (net (code "73") (name "unconnected-(U38-VB-Pad7)") (class "Default")
      (node (ref "U38") (pin "7") (pinfunction "VB_7") (pintype "passive+no_connect"))
    )
    (net (code "74") (name "unconnected-(U39-B5-Pad14)") (class "Default")
      (node (ref "U39") (pin "14") (pinfunction "B5_14") (pintype "passive+no_connect"))
    )
    (net (code "75") (name "unconnected-(U39-B6-Pad13)") (class "Default")
      (node (ref "U39") (pin "13") (pinfunction "B6_13") (pintype "passive+no_connect"))
    )
    (net (code "76") (name "unconnected-(U39-B7-Pad12)") (class "Default")
      (node (ref "U39") (pin "12") (pinfunction "B7_12") (pintype "passive+no_connect"))
    )
    (net (code "77") (name "unconnected-(U39-B8-Pad11)") (class "Default")
      (node (ref "U39") (pin "11") (pinfunction "B8_11") (pintype "passive+no_connect"))
    )
    (net (code "78") (name "unconnected-(U41-NC-Pad1)") (class "Default")
      (node (ref "U41") (pin "1") (pinfunction "NC_1") (pintype "passive+no_connect"))
    )
    (net (code "79") (name "unconnected-(U41-NC-Pad4)") (class "Default")
      (node (ref "U41") (pin "4") (pinfunction "NC_4") (pintype "power_in+no_connect"))
    )
    (net (code "80") (name "unconnected-(U41-VB-Pad7)") (class "Default")
      (node (ref "U41") (pin "7") (pinfunction "VB_7") (pintype "passive+no_connect"))
    )
    (net (code "81") (name "unconnected-(U42-NC-Pad1)") (class "Default")
      (node (ref "U42") (pin "1") (pinfunction "NC_1") (pintype "passive+no_connect"))
    )
    (net (code "82") (name "unconnected-(U42-NC-Pad4)") (class "Default")
      (node (ref "U42") (pin "4") (pinfunction "NC_4") (pintype "power_in+no_connect"))
    )
    (net (code "83") (name "unconnected-(U42-VB-Pad7)") (class "Default")
      (node (ref "U42") (pin "7") (pinfunction "VB_7") (pintype "passive+no_connect"))
    )
    (net (code "84") (name "unconnected-(U43-NC-Pad1)") (class "Default")
      (node (ref "U43") (pin "1") (pinfunction "NC_1") (pintype "passive+no_connect"))
    )
    (net (code "85") (name "unconnected-(U43-NC-Pad4)") (class "Default")
      (node (ref "U43") (pin "4") (pinfunction "NC_4") (pintype "power_in+no_connect"))
    )
    (net (code "86") (name "unconnected-(U43-VB-Pad7)") (class "Default")
      (node (ref "U43") (pin "7") (pinfunction "VB_7") (pintype "passive+no_connect"))
    )
    (net (code "87") (name "unconnected-(U45-NC-Pad1)") (class "Default")
      (node (ref "U45") (pin "1") (pinfunction "NC_1") (pintype "passive+no_connect"))
    )
    (net (code "88") (name "unconnected-(U45-NC-Pad4)") (class "Default")
      (node (ref "U45") (pin "4") (pinfunction "NC_4") (pintype "power_in+no_connect"))
    )
    (net (code "89") (name "unconnected-(U45-VB-Pad7)") (class "Default")
      (node (ref "U45") (pin "7") (pinfunction "VB_7") (pintype "passive+no_connect"))
    )
    (net (code "90") (name "unconnected-(U47-VREF-Pad5)") (class "Default")
      (node (ref "U47") (pin "5") (pinfunction "VREF_5") (pintype "passive+no_connect"))
    )
    (net (code "91") (name "unconnected-(U48-NC-Pad1)") (class "Default")
      (node (ref "U48") (pin "1") (pinfunction "NC_1") (pintype "passive+no_connect"))
    )
    (net (code "92") (name "unconnected-(U48-NC-Pad4)") (class "Default")
      (node (ref "U48") (pin "4") (pinfunction "NC_4") (pintype "power_in+no_connect"))
    )
    (net (code "93") (name "unconnected-(U48-VB-Pad7)") (class "Default")
      (node (ref "U48") (pin "7") (pinfunction "VB_7") (pintype "passive+no_connect"))
    )
    (net (code "94") (name "unconnected-(U49-NC-Pad1)") (class "Default")
      (node (ref "U49") (pin "1") (pinfunction "NC_1") (pintype "passive+no_connect"))
    )
    (net (code "95") (name "unconnected-(U49-NC-Pad4)") (class "Default")
      (node (ref "U49") (pin "4") (pinfunction "NC_4") (pintype "power_in+no_connect"))
    )
    (net (code "96") (name "unconnected-(U49-VB-Pad7)") (class "Default")
      (node (ref "U49") (pin "7") (pinfunction "VB_7") (pintype "passive+no_connect"))
    )
    (net (code "97") (name "unconnected-(U50-NC-Pad1)") (class "Default")
      (node (ref "U50") (pin "1") (pinfunction "NC_1") (pintype "passive+no_connect"))
    )
    (net (code "98") (name "unconnected-(U50-NC-Pad4)") (class "Default")
      (node (ref "U50") (pin "4") (pinfunction "NC_4") (pintype "power_in+no_connect"))
    )
    (net (code "99") (name "unconnected-(U50-VB-Pad7)") (class "Default")
      (node (ref "U50") (pin "7") (pinfunction "VB_7") (pintype "passive+no_connect"))
    )
    (net (code "100") (name "unconnected-(U52-NC-Pad1)") (class "Default")
      (node (ref "U52") (pin "1") (pinfunction "NC_1") (pintype "passive+no_connect"))
    )
    (net (code "101") (name "unconnected-(U52-NC-Pad4)") (class "Default")
      (node (ref "U52") (pin "4") (pinfunction "NC_4") (pintype "power_in+no_connect"))
    )
    (net (code "102") (name "unconnected-(U52-VB-Pad7)") (class "Default")
      (node (ref "U52") (pin "7") (pinfunction "VB_7") (pintype "passive+no_connect"))
    )
  )
)
